# LB_BIT_p3_USBPOWER-v02_rev1.net
KiCad netlist of a schematic drawn in EAGLE
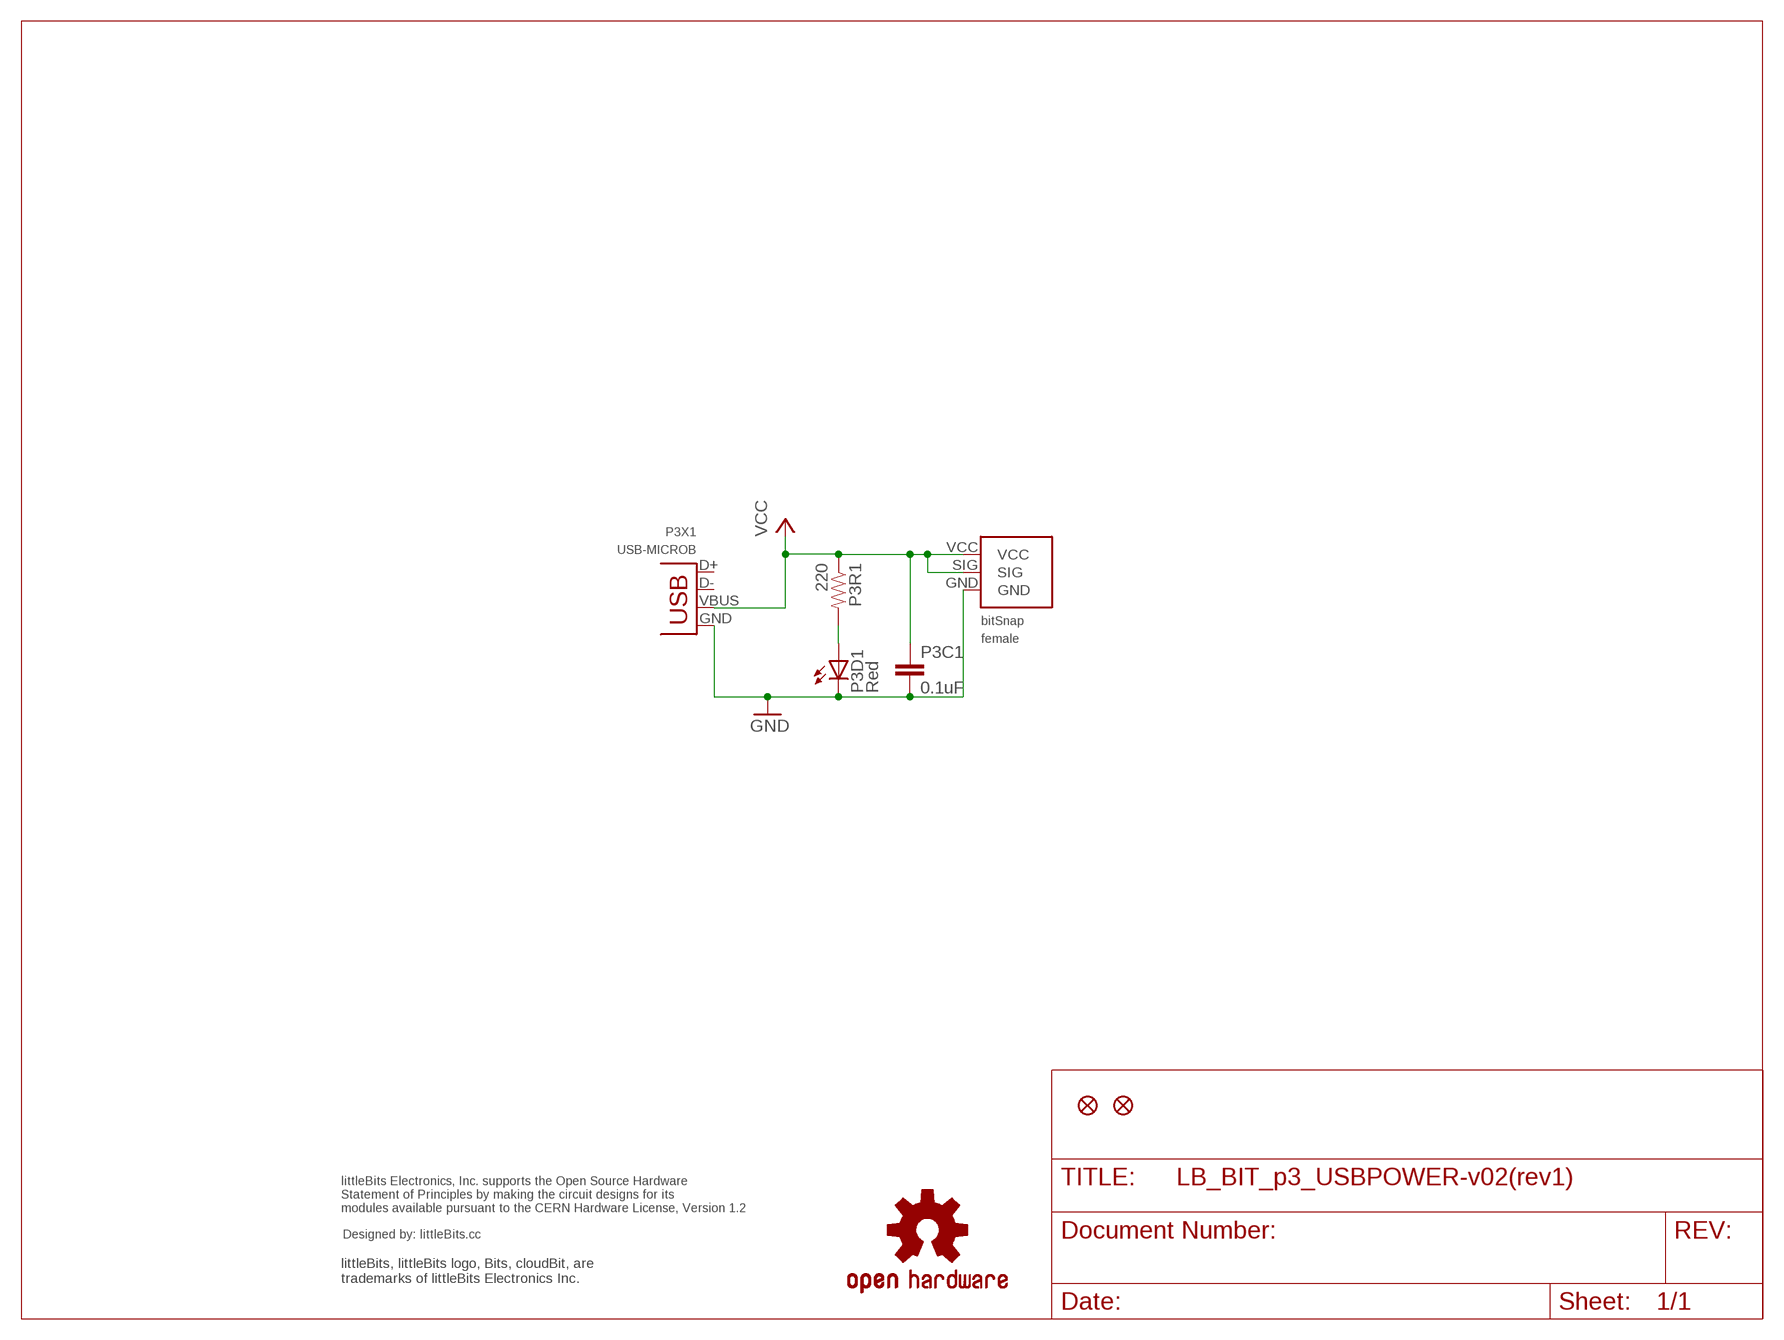
[diagram p0: schematic, sheet 1]

(export (version "E")
  (design (tool "Eeschema 10.0.6"))
  (components
    (comp (ref "P3BSF")
      (value "BITSNAP_FEMALE")
      (footprint "eagle-import:BITSNAP_FEMALE")
      (libsource (lib "eagle-import") (part "BITSNAP_FEMALE"))
    )
    (comp (ref "P3C1")
      (value "0.1uF")
      (footprint "eagle-import:0603-CAP")
      (libsource (lib "eagle-import") (part "CAP0603-CAP"))
    )
    (comp (ref "P3D1")
      (value "Red")
      (footprint "eagle-import:LED-1206")
      (libsource (lib "eagle-import") (part "LED1206"))
    )
    (comp (ref "P3FD1")
      (value "FIDUCIAL1X2")
      (footprint "eagle-import:FIDUCIAL-1X2")
      (libsource (lib "eagle-import") (part "FIDUCIAL1X2"))
    )
    (comp (ref "P3FD2")
      (value "FIDUCIAL1X2")
      (footprint "eagle-import:FIDUCIAL-1X2")
      (libsource (lib "eagle-import") (part "FIDUCIAL1X2"))
    )
    (comp (ref "P3R1")
      (value "220")
      (footprint "eagle-import:0603-RES")
      (libsource (lib "eagle-import") (part "RESISTOR0603-RES"))
    )
    (comp (ref "P3X1")
      (value "USB-MICROB")
      (footprint "eagle-import:USB-MICROB-ZX62-B-5PA(11)")
      (libsource (lib "eagle-import") (part "USB-MICROB"))
    )
    (comp (ref "U$2")
      (value "OSHWCREDIT")
      (footprint "eagle-import:OSHWCREDIT")
      (libsource (lib "eagle-import") (part "OSHWCREDIT"))
    )
    (comp (ref "U$3")
      (value "OSHW-LOGOL")
      (footprint "eagle-import:OSHW-LOGO-L")
      (libsource (lib "eagle-import") (part "OSHW-LOGOL"))
    )
  )
  (nets
    (net (code "1") (name "GND") (class "Default")
      (node (ref "P3BSF") (pin "GND") (pinfunction "GND_GND") (pintype "bidirectional"))
      (node (ref "P3C1") (pin "2") (pinfunction "2_2") (pintype "passive"))
      (node (ref "P3D1") (pin "C") (pinfunction "C_C") (pintype "passive"))
      (node (ref "P3X1") (pin "GND") (pinfunction "GND_GND") (pintype "bidirectional"))
    )
    (net (code "2") (name "Net-(P3D1-PadA)") (class "Default")
      (node (ref "P3D1") (pin "A") (pinfunction "A_A") (pintype "passive"))
      (node (ref "P3R1") (pin "2") (pinfunction "2_2") (pintype "passive"))
    )
    (net (code "3") (name "VCC") (class "Default")
      (node (ref "P3BSF") (pin "SIG") (pinfunction "SIG_SIG") (pintype "bidirectional"))
      (node (ref "P3BSF") (pin "VCC") (pinfunction "VCC_VCC") (pintype "bidirectional"))
      (node (ref "P3C1") (pin "1") (pinfunction "1_1") (pintype "passive"))
      (node (ref "P3R1") (pin "1") (pinfunction "1_1") (pintype "passive"))
      (node (ref "P3X1") (pin "VBUS") (pinfunction "VBUS_VBUS") (pintype "bidirectional"))
    )
    (net (code "4") (name "unconnected-(P3X1-PadD+)") (class "Default")
      (node (ref "P3X1") (pin "D+") (pinfunction "D+_D+") (pintype "bidirectional"))
    )
    (net (code "5") (name "unconnected-(P3X1-PadD-)") (class "Default")
      (node (ref "P3X1") (pin "D-") (pinfunction "D-_D-") (pintype "bidirectional"))
    )
  )
)
